# LED_Driver.net
KiCad netlist of a schematic drawn in Altium Designer
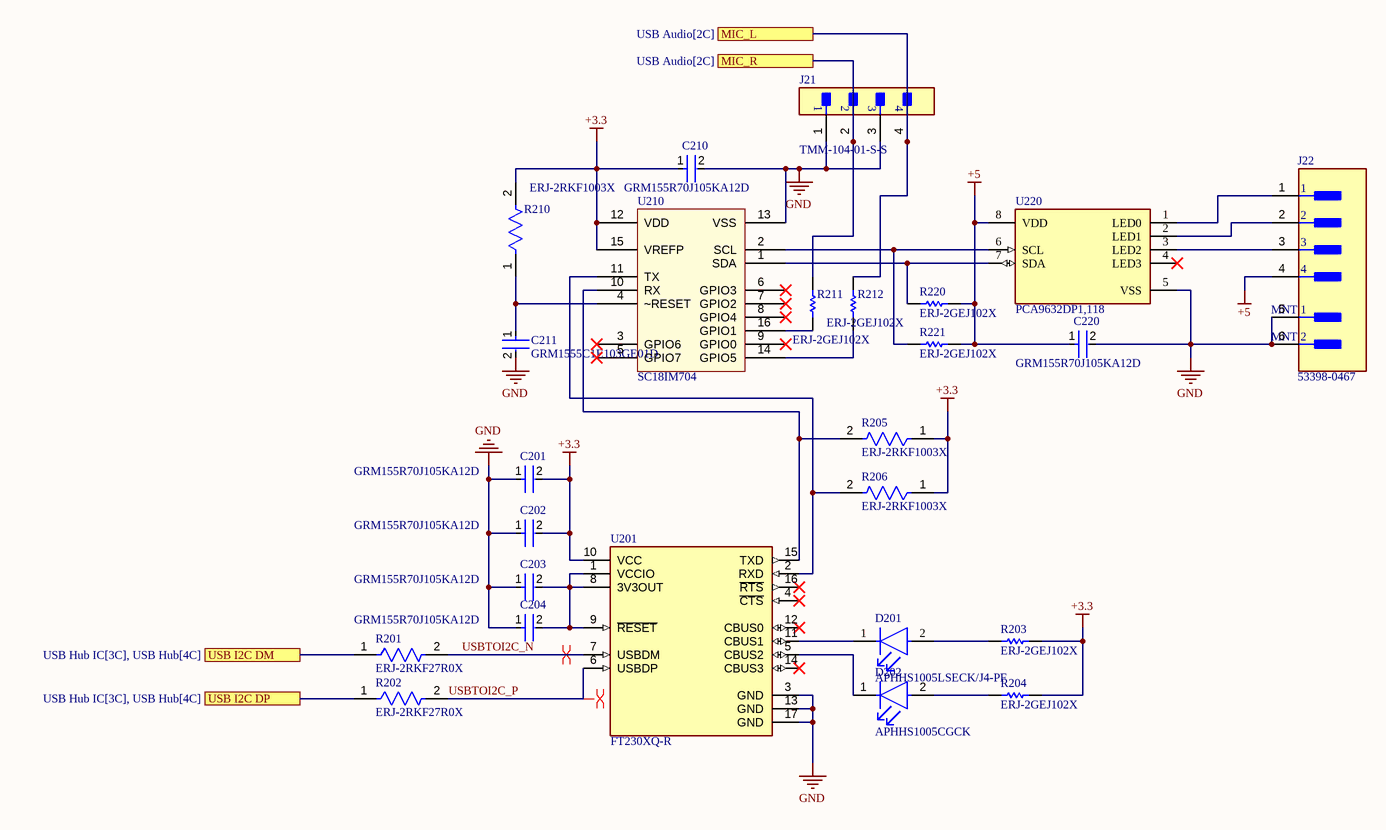
[diagram p0: LED Driver.SchDoc]

(export (version "E")
  (design (tool "Eeschema 10.0.6"))
  (components
    (comp (ref "C201")
      (value "GRM155R70J105KA12D")
      (footprint "FP-GRM155-0_05-MFG")
      (description "Chip Multilayer Ceramic Capacitors for General Purpose, 0402, 1.0uF, X7R, 15%, 10%, 6.3V")
      (fields (field (name "TOLERANCE") "10%"))
      (libsource (lib "Altium Content Vault") (part "02cd4be3c70576c341d710602a673aa"))
    )
    (comp (ref "C202")
      (value "GRM155R70J105KA12D")
      (footprint "FP-GRM155-0_05-MFG")
      (description "Chip Multilayer Ceramic Capacitors for General Purpose, 0402, 1.0uF, X7R, 15%, 10%, 6.3V")
      (fields (field (name "TOLERANCE") "10%"))
      (libsource (lib "Altium Content Vault") (part "02cd4be3c70576c341d710602a673aa"))
    )
    (comp (ref "C203")
      (value "GRM155R70J105KA12D")
      (footprint "FP-GRM155-0_05-MFG")
      (description "Chip Multilayer Ceramic Capacitors for General Purpose, 0402, 1.0uF, X7R, 15%, 10%, 6.3V")
      (fields (field (name "TOLERANCE") "10%"))
      (libsource (lib "Altium Content Vault") (part "02cd4be3c70576c341d710602a673aa"))
    )
    (comp (ref "C204")
      (value "GRM155R70J105KA12D")
      (footprint "FP-GRM155-0_05-MFG")
      (description "Chip Multilayer Ceramic Capacitors for General Purpose, 0402, 1.0uF, X7R, 15%, 10%, 6.3V")
      (fields (field (name "TOLERANCE") "10%"))
      (libsource (lib "Altium Content Vault") (part "02cd4be3c70576c341d710602a673aa"))
    )
    (comp (ref "C210")
      (value "GRM155R70J105KA12D")
      (footprint "FP-GRM155-0_05-MFG")
      (description "Chip Multilayer Ceramic Capacitors for General Purpose, 0402, 1.0uF, X7R, 15%, 10%, 6.3V")
      (fields (field (name "TOLERANCE") "10%"))
      (libsource (lib "Altium Content Vault") (part "02cd4be3c70576c341d710602a673aa"))
    )
    (comp (ref "C211")
      (value "GRM1555C1E103GE01D")
      (footprint "FP-GRM155-0_15-IPC_B")
      (description "Chip Multilayer Ceramic Capacitors for General Purpose, 0402, 10000pF, C0G, 30ppm/°C, 2%, 25V")
      (libsource (lib "Altium Content Vault") (part "b4654b650e69147ec39a6b967a45e02"))
    )
    (comp (ref "C220")
      (value "GRM155R70J105KA12D")
      (footprint "FP-GRM155-0_05-MFG")
      (description "Chip Multilayer Ceramic Capacitors for General Purpose, 0402, 1.0uF, X7R, 15%, 10%, 6.3V")
      (fields (field (name "TOLERANCE") "10%"))
      (libsource (lib "Altium Content Vault") (part "02cd4be3c70576c341d710602a673aa"))
    )
    (comp (ref "D201")
      (value "APHHS1005LSECK/J4-PF")
      (footprint "FP-APHHS1005LSECK-J4-PF-MFG")
      (description "APHHS1005LSECK/J4-PF LED Uni-Color SB. Orange 611nm 2-Pin SMD T/R")
      (libsource (lib "Altium Content Vault") (part "8706943c75ba83719d021d2fdc84c58"))
    )
    (comp (ref "D202")
      (value "APHHS1005CGCK")
      (footprint "FP-APHHS1005CGCK-MFG")
      (description "LED GREEN CLEAR CHIP SMD")
      (libsource (lib "Altium Content Vault") (part "8706943c75ba83719d021d2fdc84c58"))
    )
    (comp (ref "J21")
      (value "TMM-104-01-S-S")
      (footprint "FP-TMM-104-01-S-S-MFG")
      (description "CONN HEADER VERT 4POS 2MM")
      (libsource (lib "Altium Content Vault") (part "299a8cea1bdcbc3624fe62c390fa72c"))
    )
    (comp (ref "J22")
      (value "53398-0467")
      (footprint "FP-53398-0467-MFG")
      (description "CONN HEADER SMD 4POS 1.25MM")
      (libsource (lib "Altium Content Vault") (part "3b6f738a5616415d78381ad43816e4a"))
    )
    (comp (ref "R201")
      (value "ERJ-2RKF27R0X")
      (footprint "FP-ERJ2R-IPC_B")
      (description "RES SMD 27 OHM 1% 1/10W 0402")
      (fields (field (name "TOLERANCE") "1%"))
      (libsource (lib "Altium Content Vault") (part "8db39607336c341a927600551d01821"))
    )
    (comp (ref "R202")
      (value "ERJ-2RKF27R0X")
      (footprint "FP-ERJ2R-IPC_B")
      (description "RES SMD 27 OHM 1% 1/10W 0402")
      (fields (field (name "TOLERANCE") "1%"))
      (libsource (lib "Altium Content Vault") (part "8db39607336c341a927600551d01821"))
    )
    (comp (ref "R203")
      (value "ERJ-2GEJ102X")
      (footprint "RESC1005X40X25NL05T05")
      (fields (field (name "MANUFACTURER") "Panasonic"))
      (libsource (lib "Altium Content Vault") (part "RES"))
    )
    (comp (ref "R204")
      (value "ERJ-2GEJ102X")
      (footprint "RESC1005X40X25NL05T05")
      (fields (field (name "MANUFACTURER") "Panasonic"))
      (libsource (lib "Altium Content Vault") (part "RES"))
    )
    (comp (ref "R205")
      (value "ERJ-2RKF1003X")
      (footprint "FP-ERJ2RK-IPC_C")
      (description "RES SMD 100K OHM 1% 1/10W 0402")
      (fields (field (name "TOLERANCE") "1%"))
      (libsource (lib "Altium Content Vault") (part "1029c3af85768c4190bb7ad29bc67b5"))
    )
    (comp (ref "R206")
      (value "ERJ-2RKF1003X")
      (footprint "FP-ERJ2RK-IPC_C")
      (description "RES SMD 100K OHM 1% 1/10W 0402")
      (fields (field (name "TOLERANCE") "1%"))
      (libsource (lib "Altium Content Vault") (part "1029c3af85768c4190bb7ad29bc67b5"))
    )
    (comp (ref "R210")
      (value "ERJ-2RKF1003X")
      (footprint "FP-ERJ2RK-IPC_C")
      (description "RES SMD 100K OHM 1% 1/10W 0402")
      (fields (field (name "TOLERANCE") "1%"))
      (libsource (lib "Altium Content Vault") (part "1029c3af85768c4190bb7ad29bc67b5"))
    )
    (comp (ref "R211")
      (value "ERJ-2GEJ102X")
      (footprint "RESC1005X40X25NL05T05")
      (fields (field (name "MANUFACTURER") "Panasonic"))
      (libsource (lib "Altium Content Vault") (part "RES"))
    )
    (comp (ref "R212")
      (value "ERJ-2GEJ102X")
      (footprint "RESC1005X40X25NL05T05")
      (fields (field (name "MANUFACTURER") "Panasonic"))
      (libsource (lib "Altium Content Vault") (part "RES"))
    )
    (comp (ref "R220")
      (value "ERJ-2GEJ102X")
      (footprint "RESC1005X40X25NL05T05")
      (fields (field (name "MANUFACTURER") "Panasonic"))
      (libsource (lib "Altium Content Vault") (part "RES"))
    )
    (comp (ref "R221")
      (value "ERJ-2GEJ102X")
      (footprint "RESC1005X40X25NL05T05")
      (fields (field (name "MANUFACTURER") "Panasonic"))
      (libsource (lib "Altium Content Vault") (part "RES"))
    )
    (comp (ref "U201")
      (value "FT230XQ-R")
      (footprint "FP-QFN-16-MFG")
      (description "IC USB SERIAL BASIC UART 16QFN")
      (libsource (lib "Altium Content Vault") (part "29d2eb9587eff32afae5da052de4085"))
    )
    (comp (ref "U210")
      (value "SC18IM704")
      (footprint "TSSOP-16")
      (libsource (lib "Schlib1") (part "SC18IM704"))
    )
    (comp (ref "U220")
      (value "PCA9632DP1,118")
      (footprint "FP-SOT505-1-IPC_C")
      (description "IC LED DRVR LIN DIM 25MA 8TSSOP")
      (libsource (lib "Altium Content Vault") (part "d32034a899f7f8d8d1e83d0e16b4e39"))
    )
  )
  (nets
    (net (code "1") (name "+3.3") (class "Default")
      (node (ref "C201") (pin "2") (pinfunction "2_2") (pintype "passive"))
      (node (ref "C202") (pin "2") (pinfunction "2_2") (pintype "passive"))
      (node (ref "C210") (pin "1") (pinfunction "1_1") (pintype "passive"))
      (node (ref "R203") (pin "2") (pinfunction "2_2") (pintype "passive"))
      (node (ref "R204") (pin "2") (pinfunction "2_2") (pintype "passive"))
      (node (ref "R205") (pin "1") (pinfunction "1_1") (pintype "passive"))
      (node (ref "R206") (pin "1") (pinfunction "1_1") (pintype "passive"))
      (node (ref "R210") (pin "2") (pinfunction "2_2") (pintype "passive"))
      (node (ref "U201") (pin "10") (pinfunction "VCC_10") (pintype "power_in"))
      (node (ref "U210") (pin "12") (pinfunction "VDD_12") (pintype "passive"))
      (node (ref "U210") (pin "15") (pinfunction "VREFP_15") (pintype "passive"))
    )
    (net (code "2") (name "+5") (class "Default")
      (node (ref "C220") (pin "1") (pinfunction "1_1") (pintype "passive"))
      (node (ref "J22") (pin "4") (pinfunction "4_4") (pintype "passive"))
      (node (ref "R220") (pin "2") (pinfunction "2_2") (pintype "passive"))
      (node (ref "R221") (pin "2") (pinfunction "2_2") (pintype "passive"))
      (node (ref "U220") (pin "8") (pinfunction "VDD_8") (pintype "power_in"))
    )
    (net (code "3") (name "/MIC_L") (class "Default")
      (node (ref "J21") (pin "4") (pinfunction "4_4") (pintype "passive"))
      (node (ref "R212") (pin "2") (pinfunction "2_2") (pintype "passive"))
    )
    (net (code "4") (name "/MIC_R") (class "Default")
      (node (ref "J21") (pin "2") (pinfunction "2_2") (pintype "passive"))
      (node (ref "R211") (pin "2") (pinfunction "2_2") (pintype "passive"))
    )
    (net (code "5") (name "/USB I2C DM") (class "Default")
      (node (ref "R201") (pin "1") (pinfunction "1_1") (pintype "passive"))
    )
    (net (code "6") (name "/USB I2C DP") (class "Default")
      (node (ref "R202") (pin "1") (pinfunction "1_1") (pintype "passive"))
    )
    (net (code "7") (name "/USBTOI2C_N") (class "Default")
      (node (ref "R201") (pin "2") (pinfunction "2_2") (pintype "passive"))
      (node (ref "U201") (pin "7") (pinfunction "USBDM_7") (pintype "input"))
    )
    (net (code "8") (name "/USBTOI2C_P") (class "Default")
      (node (ref "R202") (pin "2") (pinfunction "2_2") (pintype "passive"))
      (node (ref "U201") (pin "6") (pinfunction "USBDP_6") (pintype "input"))
    )
    (net (code "9") (name "GND") (class "Default")
      (node (ref "C201") (pin "1") (pinfunction "1_1") (pintype "passive"))
      (node (ref "C202") (pin "1") (pinfunction "1_1") (pintype "passive"))
      (node (ref "C203") (pin "1") (pinfunction "1_1") (pintype "passive"))
      (node (ref "C204") (pin "1") (pinfunction "1_1") (pintype "passive"))
      (node (ref "C210") (pin "2") (pinfunction "2_2") (pintype "passive"))
      (node (ref "C211") (pin "2") (pinfunction "2_2") (pintype "passive"))
      (node (ref "C220") (pin "2") (pinfunction "2_2") (pintype "passive"))
      (node (ref "J21") (pin "1") (pinfunction "1_1") (pintype "passive"))
      (node (ref "J21") (pin "3") (pinfunction "3_3") (pintype "passive"))
      (node (ref "J22") (pin "5") (pinfunction "MNT_1_5") (pintype "passive"))
      (node (ref "J22") (pin "6") (pinfunction "MNT_2_6") (pintype "passive"))
      (node (ref "U201") (pin "13") (pinfunction "GND_13") (pintype "power_in"))
      (node (ref "U201") (pin "17") (pinfunction "GND_17") (pintype "power_in"))
      (node (ref "U201") (pin "3") (pinfunction "GND_3") (pintype "power_in"))
      (node (ref "U210") (pin "13") (pinfunction "VSS_13") (pintype "passive"))
      (node (ref "U220") (pin "5") (pinfunction "VSS_5") (pintype "power_in"))
    )
    (net (code "10") (name "Net-(D201-A)") (class "Default")
      (node (ref "D201") (pin "2") (pinfunction "A_2") (pintype "passive"))
      (node (ref "R203") (pin "1") (pinfunction "1_1") (pintype "passive"))
    )
    (net (code "11") (name "Net-(D201-C)") (class "Default")
      (node (ref "D201") (pin "1") (pinfunction "C_1") (pintype "passive"))
      (node (ref "U201") (pin "11") (pinfunction "CBUS1_11") (pintype "bidirectional"))
    )
    (net (code "12") (name "Net-(D202-A)") (class "Default")
      (node (ref "D202") (pin "2") (pinfunction "A_2") (pintype "passive"))
      (node (ref "R204") (pin "1") (pinfunction "1_1") (pintype "passive"))
    )
    (net (code "13") (name "Net-(D202-C)") (class "Default")
      (node (ref "D202") (pin "1") (pinfunction "C_1") (pintype "passive"))
      (node (ref "U201") (pin "5") (pinfunction "CBUS2_5") (pintype "bidirectional"))
    )
    (net (code "14") (name "Net-(U201-3V3OUT)") (class "Default")
      (node (ref "C203") (pin "2") (pinfunction "2_2") (pintype "passive"))
      (node (ref "C204") (pin "2") (pinfunction "2_2") (pintype "passive"))
      (node (ref "U201") (pin "1") (pinfunction "VCCIO_1") (pintype "power_in"))
      (node (ref "U201") (pin "8") (pinfunction "3V3OUT_8") (pintype "power_in"))
      (node (ref "U201") (pin "9") (pinfunction "~{RESET}_9") (pintype "input"))
    )
    (net (code "15") (name "Net-(U201-RXD)") (class "Default")
      (node (ref "R206") (pin "2") (pinfunction "2_2") (pintype "passive"))
      (node (ref "U201") (pin "2") (pinfunction "RXD_2") (pintype "input"))
      (node (ref "U210") (pin "11") (pinfunction "TX_11") (pintype "passive"))
    )
    (net (code "16") (name "Net-(U201-TXD)") (class "Default")
      (node (ref "R205") (pin "2") (pinfunction "2_2") (pintype "passive"))
      (node (ref "U201") (pin "15") (pinfunction "TXD_15") (pintype "output"))
      (node (ref "U210") (pin "10") (pinfunction "RX_10") (pintype "passive"))
    )
    (net (code "17") (name "Net-(U210-GPIO1)") (class "Default")
      (node (ref "R211") (pin "1") (pinfunction "1_1") (pintype "passive"))
      (node (ref "U210") (pin "16") (pinfunction "GPIO1_16") (pintype "passive"))
    )
    (net (code "18") (name "Net-(U210-GPIO5)") (class "Default")
      (node (ref "R212") (pin "1") (pinfunction "1_1") (pintype "passive"))
      (node (ref "U210") (pin "14") (pinfunction "GPIO5_14") (pintype "passive"))
    )
    (net (code "19") (name "Net-(U210-SCL)") (class "Default")
      (node (ref "R221") (pin "1") (pinfunction "1_1") (pintype "passive"))
      (node (ref "U210") (pin "2") (pinfunction "SCL_2") (pintype "passive"))
      (node (ref "U220") (pin "6") (pinfunction "SCL_6") (pintype "input"))
    )
    (net (code "20") (name "Net-(U210-SDA)") (class "Default")
      (node (ref "R220") (pin "1") (pinfunction "1_1") (pintype "passive"))
      (node (ref "U210") (pin "1") (pinfunction "SDA_1") (pintype "passive"))
      (node (ref "U220") (pin "7") (pinfunction "SDA_7") (pintype "bidirectional"))
    )
    (net (code "21") (name "Net-(U210-~RESET)") (class "Default")
      (node (ref "C211") (pin "1") (pinfunction "1_1") (pintype "passive"))
      (node (ref "R210") (pin "1") (pinfunction "1_1") (pintype "passive"))
      (node (ref "U210") (pin "4") (pinfunction "~RESET_4") (pintype "passive"))
    )
    (net (code "22") (name "Net-(U220-LED0)") (class "Default")
      (node (ref "J22") (pin "1") (pinfunction "1_1") (pintype "passive"))
      (node (ref "U220") (pin "1") (pinfunction "LED0_1") (pintype "passive"))
    )
    (net (code "23") (name "Net-(U220-LED1)") (class "Default")
      (node (ref "J22") (pin "2") (pinfunction "2_2") (pintype "passive"))
      (node (ref "U220") (pin "2") (pinfunction "LED1_2") (pintype "passive"))
    )
    (net (code "24") (name "Net-(U220-LED2)") (class "Default")
      (node (ref "J22") (pin "3") (pinfunction "3_3") (pintype "passive"))
      (node (ref "U220") (pin "3") (pinfunction "LED2_3") (pintype "passive"))
    )
    (net (code "25") (name "unconnected-(U201-CBUS0-Pad12)") (class "Default")
      (node (ref "U201") (pin "12") (pinfunction "CBUS0_12") (pintype "bidirectional+no_connect"))
    )
    (net (code "26") (name "unconnected-(U201-CBUS3-Pad14)") (class "Default")
      (node (ref "U201") (pin "14") (pinfunction "CBUS3_14") (pintype "bidirectional+no_connect"))
    )
    (net (code "27") (name "unconnected-(U201-~{CTS}-Pad4)") (class "Default")
      (node (ref "U201") (pin "4") (pinfunction "~{CTS}_4") (pintype "input+no_connect"))
    )
    (net (code "28") (name "unconnected-(U201-~{RTS}-Pad16)") (class "Default")
      (node (ref "U201") (pin "16") (pinfunction "~{RTS}_16") (pintype "output+no_connect"))
    )
    (net (code "29") (name "unconnected-(U210-GPIO0-Pad9)") (class "Default")
      (node (ref "U210") (pin "9") (pinfunction "GPIO0_9") (pintype "passive+no_connect"))
    )
    (net (code "30") (name "unconnected-(U210-GPIO2-Pad7)") (class "Default")
      (node (ref "U210") (pin "7") (pinfunction "GPIO2_7") (pintype "passive+no_connect"))
    )
    (net (code "31") (name "unconnected-(U210-GPIO3-Pad6)") (class "Default")
      (node (ref "U210") (pin "6") (pinfunction "GPIO3_6") (pintype "passive+no_connect"))
    )
    (net (code "32") (name "unconnected-(U210-GPIO4-Pad8)") (class "Default")
      (node (ref "U210") (pin "8") (pinfunction "GPIO4_8") (pintype "passive+no_connect"))
    )
    (net (code "33") (name "unconnected-(U210-GPIO6-Pad3)") (class "Default")
      (node (ref "U210") (pin "3") (pinfunction "GPIO6_3") (pintype "passive+no_connect"))
    )
    (net (code "34") (name "unconnected-(U210-GPIO7-Pad5)") (class "Default")
      (node (ref "U210") (pin "5") (pinfunction "GPIO7_5") (pintype "passive+no_connect"))
    )
    (net (code "35") (name "unconnected-(U220-LED3-Pad4)") (class "Default")
      (node (ref "U220") (pin "4") (pinfunction "LED3_4") (pintype "passive+no_connect"))
    )
  )
)
